# Power.net
KiCad netlist of a schematic drawn in Altium Designer
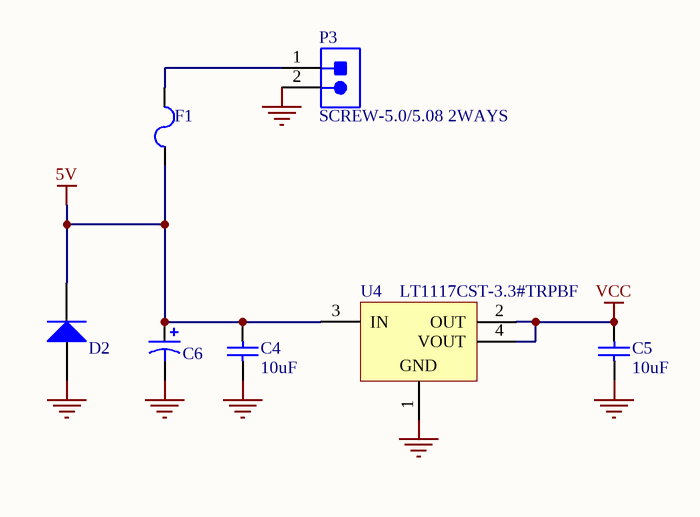
[diagram p0: Power.SchDoc]

(export (version "E")
  (design (tool "Eeschema 10.0.6"))
  (components
    (comp (ref "C4")
      (value "10uF")
      (footprint "CAPC1206(3216)130_L")
      (fields (field (name "TOLERANCE") "-20% to +80%"))
      (libsource (lib "Altium Content Vault") (part "CAP"))
    )
    (comp (ref "C5")
      (value "10uF")
      (footprint "CAPC1206(3216)130_L")
      (fields (field (name "TOLERANCE") "-20% to +80%"))
      (libsource (lib "Altium Content Vault") (part "CAP"))
    )
    (comp (ref "C6")
      (value "ECA-1HM470")
      (footprint "PNSC-ECA-1HM470")
      (description "CAP ALUM 47UF 50V 20% RADIAL")
      (libsource (lib "Altium Content Vault") (part "CAP-P-2"))
    )
    (comp (ref "D2")
      (value "MMSD4148T3G")
      (footprint "ONSC-SOD123-2-425G-04_V")
      (description "Switching Diode, 100 V, 200 mA, -55 to 150 degC, 2-Pin SOD123 (425), RoHS, Tape and Reel")
      (fields (field (name "MANUFACTURER") "ON Semiconductor"))
      (libsource (lib "Altium Content Vault") (part "ONSC-MMSD4148-SOD123-2"))
    )
    (comp (ref "F1")
      (value "1206L012WR")
      (footprint "LFUS-1206L012WR_V")
      (description "POLY-FUSE(R) Resettable PTC, 30 V, -40 to 85 degC, 2-Pin SMD, RoHS, Tape and Reel")
      (fields (field (name "MANUFACTURER") "Littelfuse"))
      (libsource (lib "Altium Content Vault") (part "FUSE-2"))
    )
    (comp (ref "P3")
      (value "SCREW-5.0/5.08 2WAYS")
      (footprint "SCREW-5.0-2WAYS_V")
      (description "Socket, Screw Terminal Block, 2 Way, 5.0 mm Pitch, 90 Degree Angle, Through-Hole")
      (fields (field (name "MANUFACTURER") "No Vendor"))
      (libsource (lib "Altium Content Vault") (part "SCREW-2WAYS"))
    )
    (comp (ref "U4")
      (value "LT1117CST-3.3#TRPBF")
      (footprint "LT-ST-3-SOT-223_N")
      (description "LDO Fixed 3.3V")
      (fields
        (field (name "PARTNUMBER") "LT1117CST-5#TRPBF")
        (field (name "MANUFACTURER") "Linear Technology")
      )
      (libsource (lib "Altium Content Vault") (part "LT-LT1117-3_B"))
    )
  )
  (nets
    (net (code "1") (name "5V") (class "Default")
      (node (ref "C4") (pin "2") (pinfunction "2_2") (pintype "passive"))
      (node (ref "C6") (pin "1") (pinfunction "+_1") (pintype "passive"))
      (node (ref "D2") (pin "1") (pinfunction "CATHODE_1") (pintype "passive"))
      (node (ref "F1") (pin "1") (pinfunction "1_1") (pintype "passive"))
      (node (ref "U4") (pin "3") (pinfunction "IN_3") (pintype "power_in"))
    )
    (net (code "2") (name "GND") (class "Default")
      (node (ref "C4") (pin "1") (pinfunction "1_1") (pintype "passive"))
      (node (ref "C5") (pin "1") (pinfunction "1_1") (pintype "passive"))
      (node (ref "C6") (pin "2") (pinfunction "-_2") (pintype "passive"))
      (node (ref "D2") (pin "2") (pinfunction "ANODE_2") (pintype "passive"))
      (node (ref "P3") (pin "2") (pinfunction "2_2") (pintype "passive"))
      (node (ref "U4") (pin "1") (pinfunction "GND_1") (pintype "power_in"))
    )
    (net (code "3") (name "Net-(F1-Pad2)") (class "Default")
      (node (ref "F1") (pin "2") (pinfunction "2_2") (pintype "passive"))
      (node (ref "P3") (pin "1") (pinfunction "1_1") (pintype "passive"))
    )
    (net (code "4") (name "VCC") (class "Default")
      (node (ref "C5") (pin "2") (pinfunction "2_2") (pintype "passive"))
      (node (ref "U4") (pin "2") (pinfunction "OUT_2") (pintype "power_in"))
      (node (ref "U4") (pin "4") (pinfunction "VOUT_4") (pintype "power_in"))
    )
  )
)
